# RF_AMPL_002.net
KiCad netlist of a schematic drawn in Altium Designer
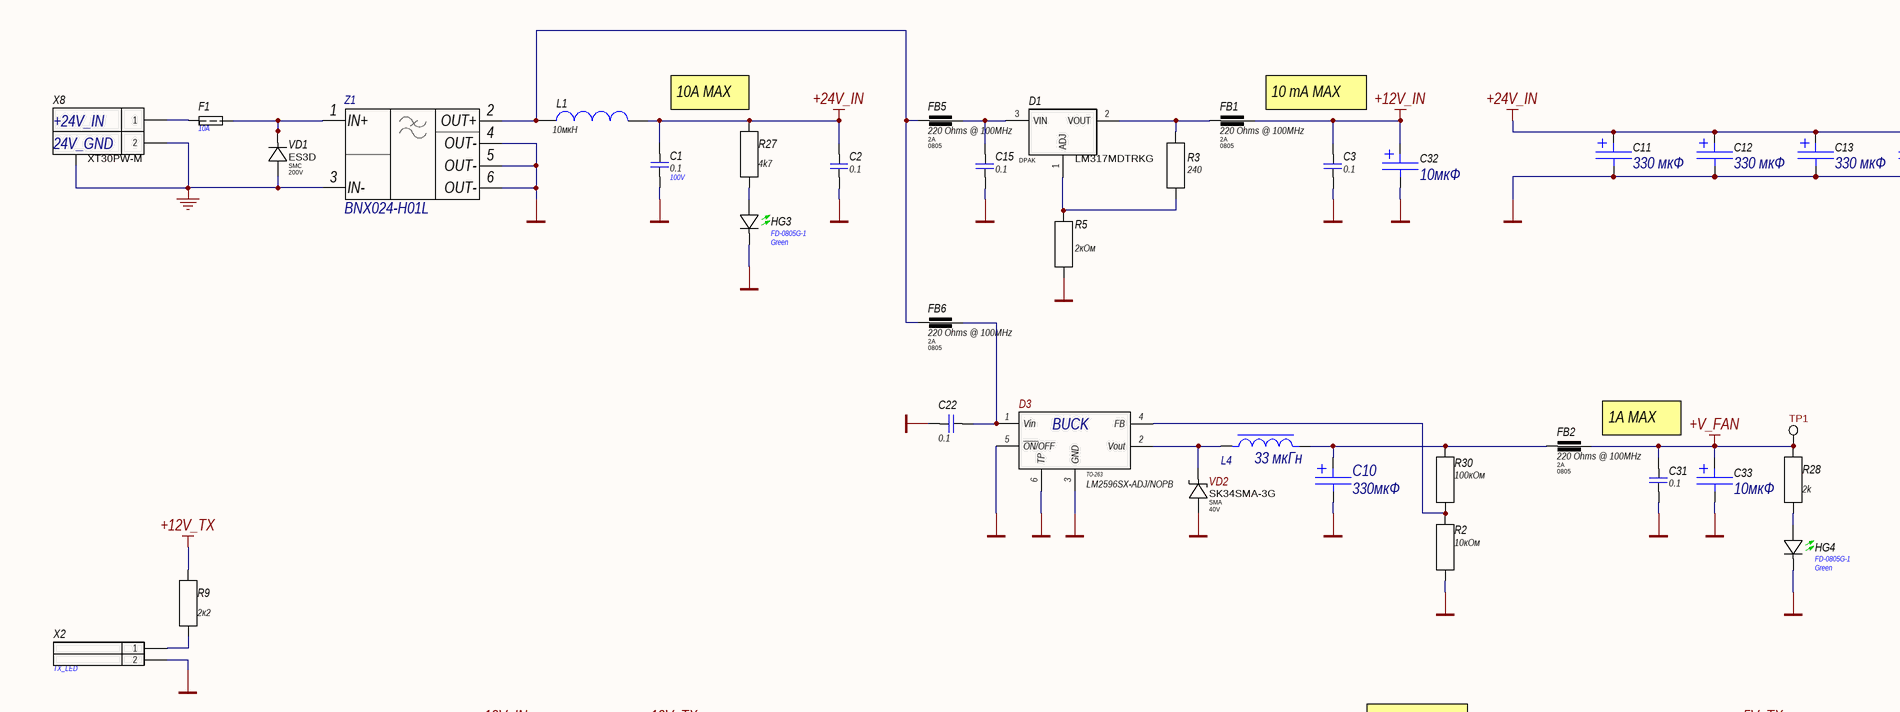
[diagram p0: RF_AMPL_002.SchDoc, top left]
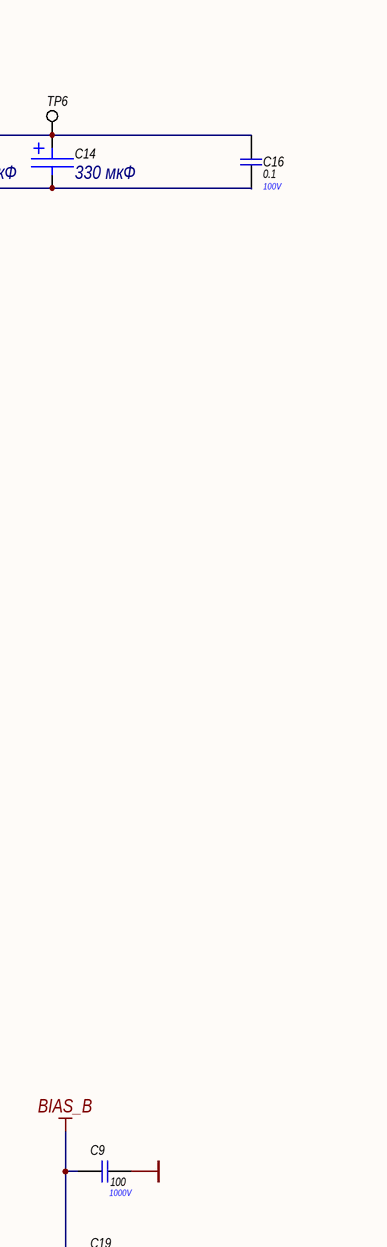
[diagram p1: RF_AMPL_002.SchDoc, top right]
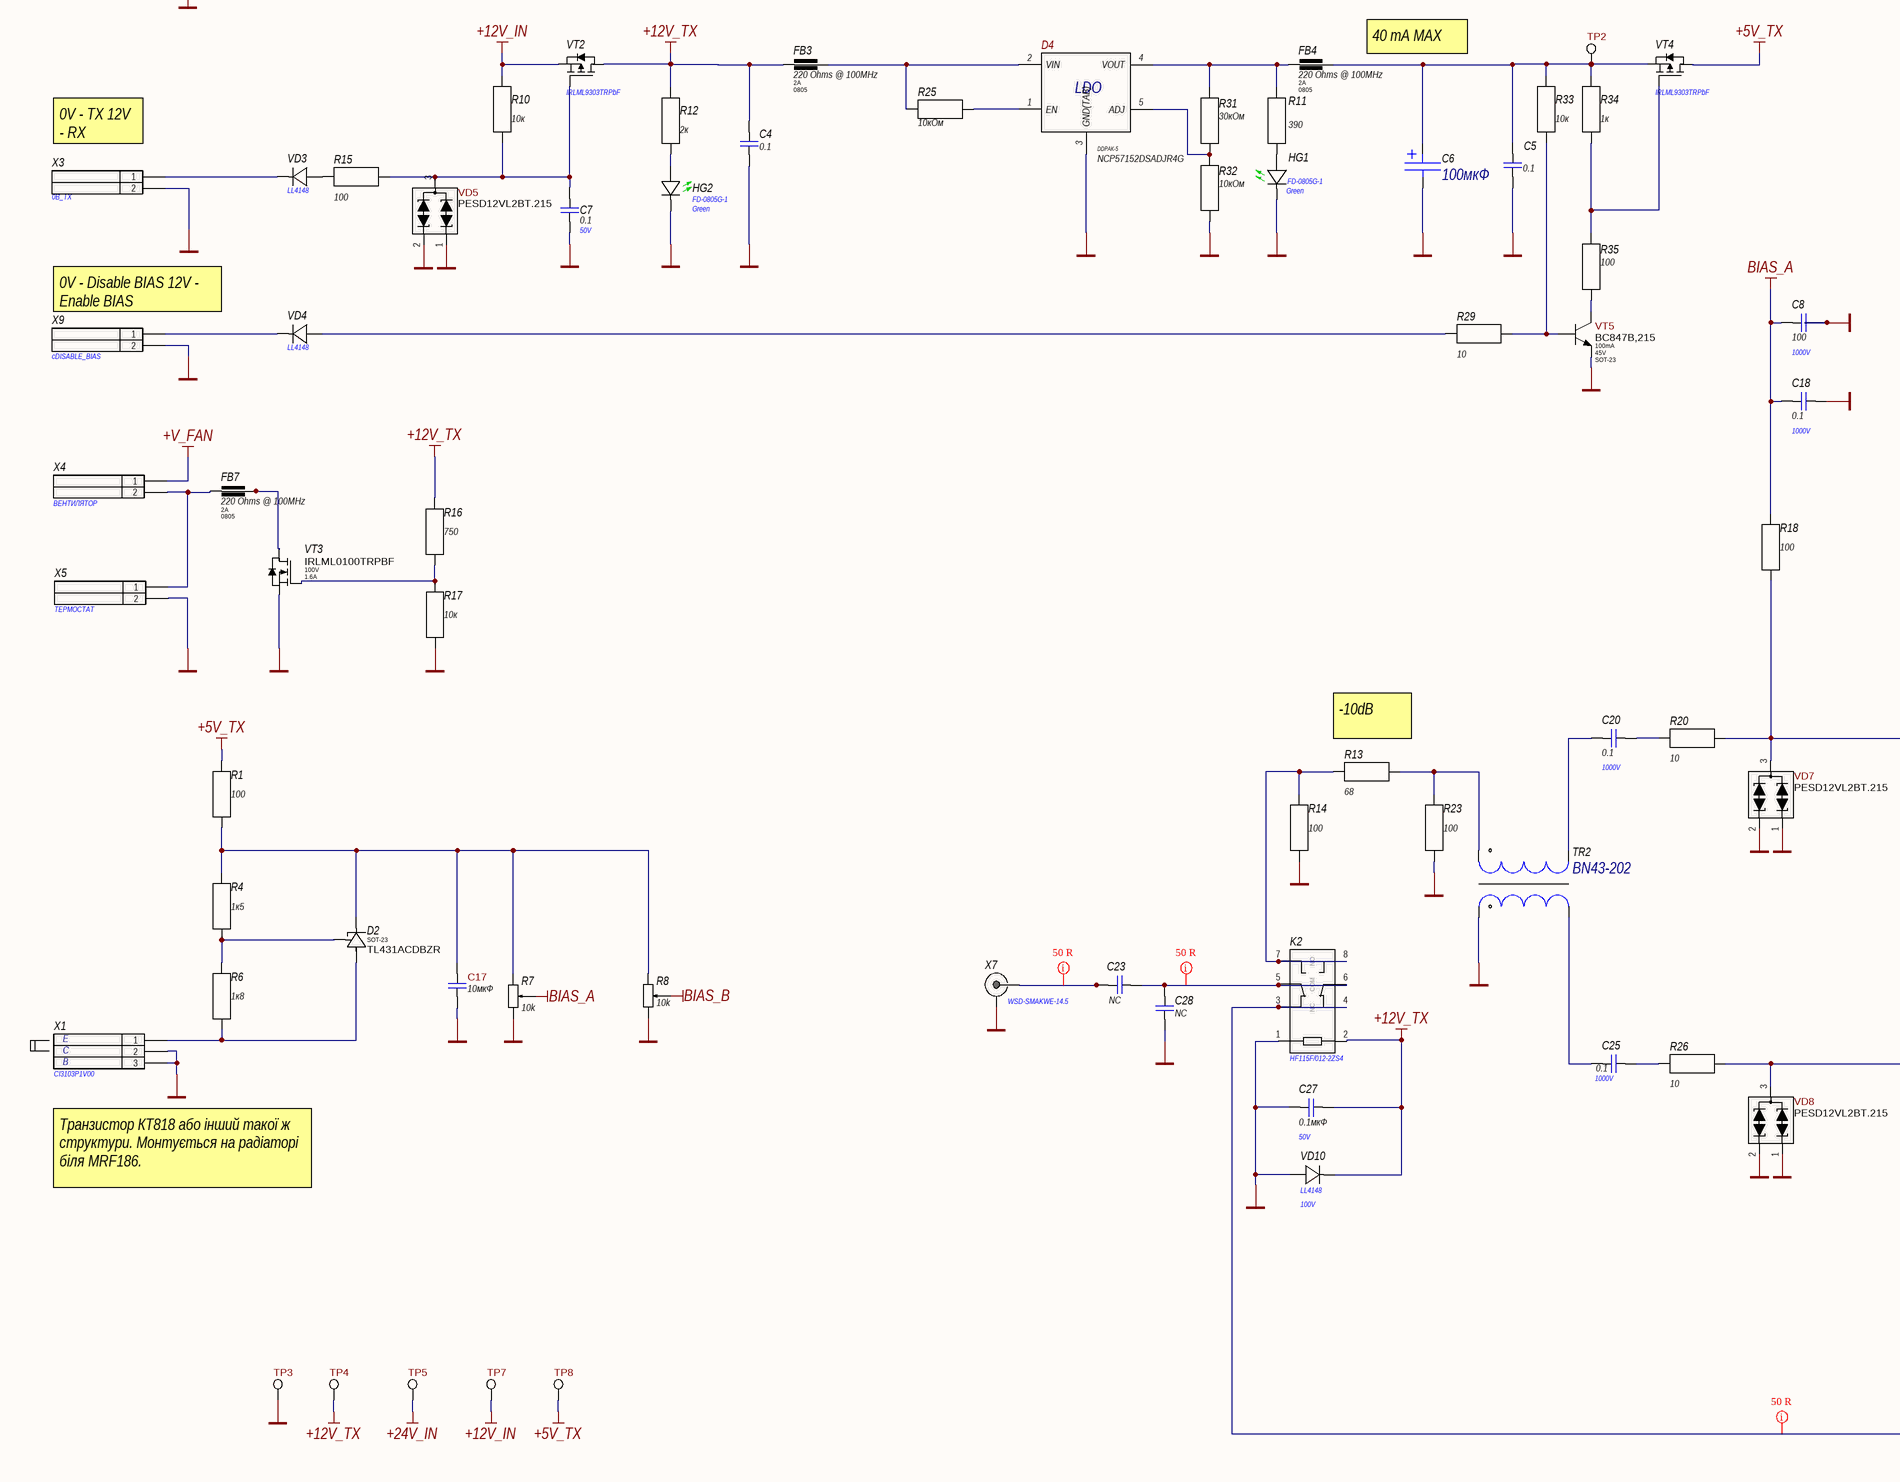
[diagram p2: RF_AMPL_002.SchDoc, bottom left]
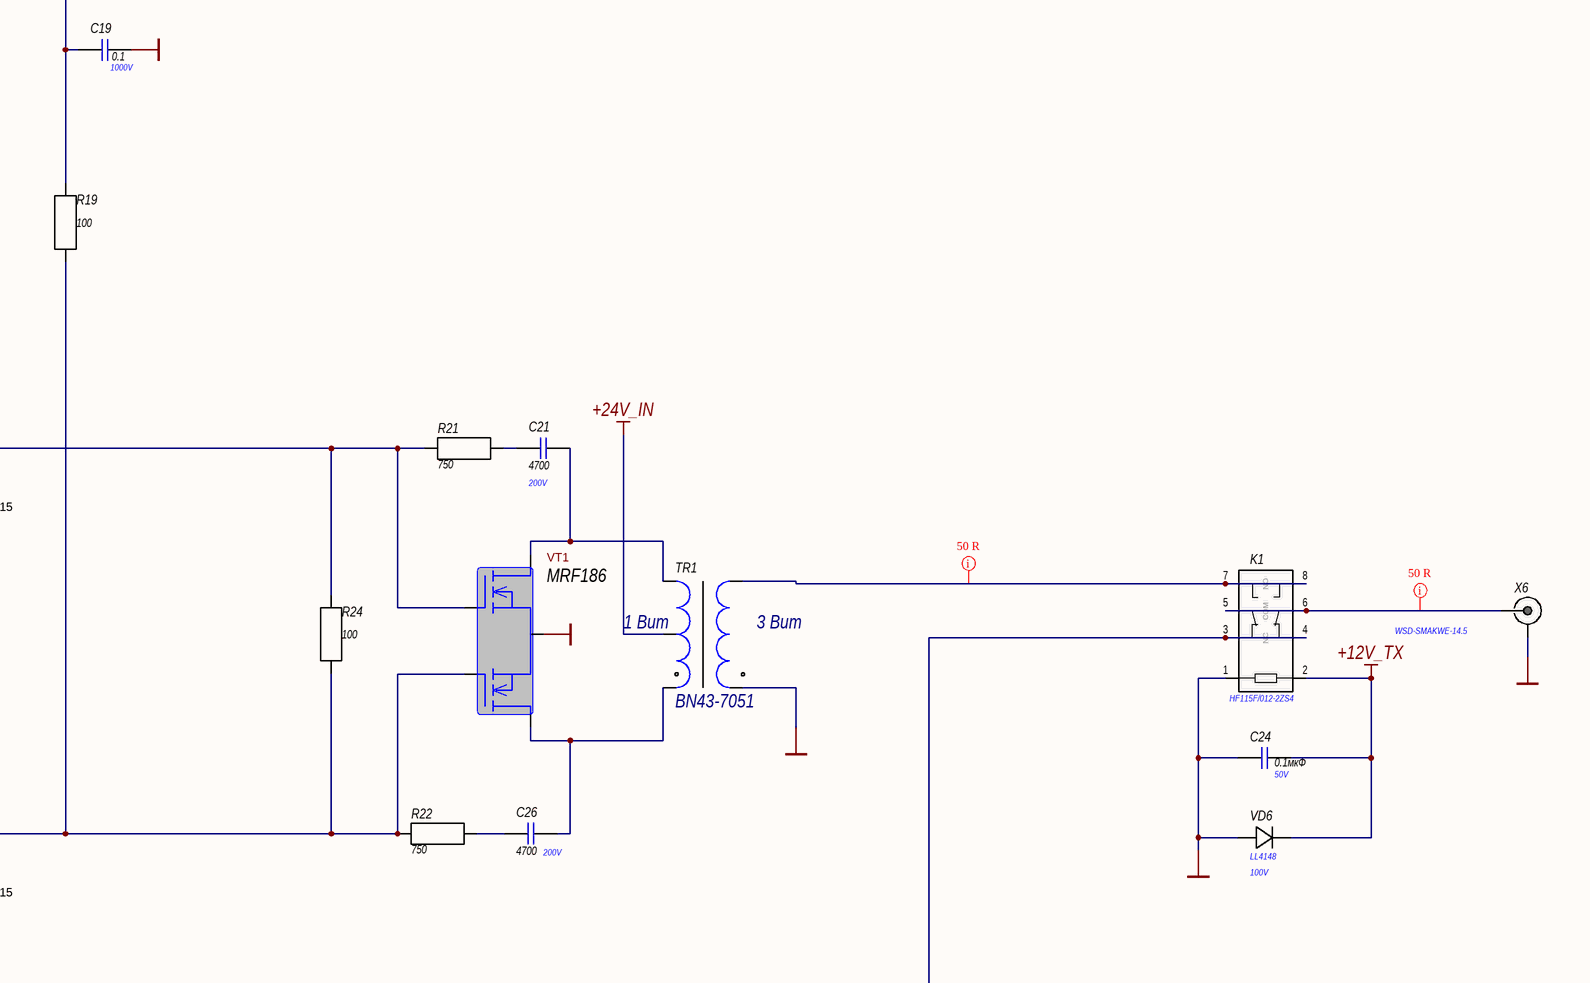
[diagram p3: RF_AMPL_002.SchDoc, bottom right]

(export (version "E")
  (design (tool "Eeschema 10.0.6"))
  (components
    (comp (ref "C1")
      (value "0.1")
      (footprint "C_CERAMIC_1206_MED")
      (description "1nF 1000V X7R ±10% 1206 Ceramic Capacitor RoHS")
      (fields
        (field (name "VOLTAGE") "100V")
        (field (name "PART NUMBER") "1206B102K102CG")
        (field (name "MANUFACTURER") "Walsin")
      )
      (libsource (lib "vitech_capacitors") (part "1206B102K102CG"))
    )
    (comp (ref "C2")
      (value "0.1")
      (footprint "C_CERAMIC_1206_MED")
      (description "1nF 1000V X7R ±10% 1206 Ceramic Capacitor RoHS")
      (fields (field (name "VOLTAGE") "100V") (field (name "PART NUMBER") "1206B102K102CG"))
      (libsource (lib "vitech_capacitors") (part "1206B102K102CG"))
    )
    (comp (ref "C3")
      (value "0.1")
      (footprint "C_CERAMIC_1206_MED")
      (description "1nF 1000V X7R ±10% 1206 Ceramic Capacitor RoHS")
      (fields (field (name "VOLTAGE") "100V") (field (name "PART NUMBER") "1206B102K102CG"))
      (libsource (lib "vitech_capacitors") (part "1206B102K102CG"))
    )
    (comp (ref "C4")
      (value "0.1")
      (footprint "C_CERAMIC_1206_MED")
      (description "1nF 1000V X7R ±10% 1206 Ceramic Capacitor RoHS")
      (fields (field (name "VOLTAGE") "100V") (field (name "PART NUMBER") "1206B102K102CG"))
      (libsource (lib "vitech_capacitors") (part "1206B102K102CG"))
    )
    (comp (ref "C5")
      (value "0.1")
      (footprint "C_CERAMIC_1206_MED")
      (description "1nF 1000V X7R ±10% 1206 Ceramic Capacitor RoHS")
      (fields (field (name "VOLTAGE") "100V") (field (name "PART NUMBER") "1206B102K102CG"))
      (libsource (lib "vitech_capacitors") (part "1206B102K102CG"))
    )
    (comp (ref "C6")
      (value "100мкФ")
      (footprint "CAPM_CASE_D_7.3x4.3x3.1mm")
      (description "Capacitor Tantalum *pF ±*% *V Case D")
      (fields (field (name "MANUFACTURER") "AVX") (field (name "PART NUMBER") "TAJD107M016R"))
      (libsource (lib "Passive") (part "CAP_TANTALUM_POLAR_CASE_D"))
    )
    (comp (ref "C7")
      (value "0.1")
      (footprint "C_CERAMIC_1206_MED")
      (description "1nF 1000V X7R ±10% 1206 Ceramic Capacitor RoHS")
      (fields
        (field (name "VOLTAGE") "50V")
        (field (name "PART NUMBER") "1206B102K102CG")
        (field (name "MANUFACTURER") "Walsin")
      )
      (libsource (lib "vitech_capacitors") (part "1206B102K102CG"))
    )
    (comp (ref "C8")
      (value "100")
      (footprint "C_CERAMIC_1206_MED")
      (description "1nF 1000V X7R ±10% 1206 Ceramic Capacitor RoHS")
      (fields
        (field (name "VOLTAGE") "1000V")
        (field (name "PART NUMBER") "1206B102K102CG")
        (field (name "MANUFACTURER") "Walsin")
      )
      (libsource (lib "vitech_capacitors") (part "1206B102K102CG"))
    )
    (comp (ref "C9")
      (value "100")
      (footprint "C_CERAMIC_1206_MED")
      (description "1nF 1000V X7R ±10% 1206 Ceramic Capacitor RoHS")
      (fields
        (field (name "VOLTAGE") "1000V")
        (field (name "PART NUMBER") "1206B102K102CG")
        (field (name "MANUFACTURER") "Walsin")
      )
      (libsource (lib "vitech_capacitors") (part "1206B102K102CG"))
    )
    (comp (ref "C10")
      (value "330мкФ")
      (footprint "CAPA_CASE_F_Panasonic_FT")
      (description "Capacitor Electrolytic *pF ±*% *V Case F")
      (fields (field (name "MANUFACTURER") "Panasonic") (field (name "PART NUMBER") "EEEFK1C331P"))
      (libsource (lib "Passive") (part "CAP_ELECTROLYTIC_POLAR_CASE_F_Panasonic_FT"))
    )
    (comp (ref "C11")
      (value "330 мкФ")
      (footprint "CAPA_CASE_G_10.4x10.4x10.5mm")
      (description "Capacitor Electrolytic *pF ±*% *V Case G")
      (fields (field (name "TOLERANCE") "±*%") (field (name "VOLTAGE") "*В"))
      (libsource (lib "Passive") (part "CAP_ELECTROLYTIC_POLAR_CASE_G"))
    )
    (comp (ref "C12")
      (value "330 мкФ")
      (footprint "CAPA_CASE_G_10.4x10.4x10.5mm")
      (description "Capacitor Electrolytic *pF ±*% *V Case G")
      (fields (field (name "TOLERANCE") "±*%") (field (name "VOLTAGE") "*В"))
      (libsource (lib "Passive") (part "CAP_ELECTROLYTIC_POLAR_CASE_G"))
    )
    (comp (ref "C13")
      (value "330 мкФ")
      (footprint "CAPA_CASE_G_10.4x10.4x10.5mm")
      (description "Capacitor Electrolytic *pF ±*% *V Case G")
      (fields (field (name "TOLERANCE") "±*%") (field (name "VOLTAGE") "*В"))
      (libsource (lib "Passive") (part "CAP_ELECTROLYTIC_POLAR_CASE_G"))
    )
    (comp (ref "C14")
      (value "330 мкФ")
      (footprint "CAPA_CASE_G_10.4x10.4x10.5mm")
      (description "Capacitor Electrolytic *pF ±*% *V Case G")
      (fields (field (name "TOLERANCE") "±*%") (field (name "VOLTAGE") "*В"))
      (libsource (lib "Passive") (part "CAP_ELECTROLYTIC_POLAR_CASE_G"))
    )
    (comp (ref "C15")
      (value "0.1")
      (footprint "C_CERAMIC_1206_MED")
      (description "1nF 1000V X7R ±10% 1206 Ceramic Capacitor RoHS")
      (fields (field (name "VOLTAGE") "100V") (field (name "PART NUMBER") "1206B102K102CG"))
      (libsource (lib "vitech_capacitors") (part "1206B102K102CG"))
    )
    (comp (ref "C16")
      (value "0.1")
      (footprint "C_CERAMIC_1206_MED")
      (description "1nF 1000V X7R ±10% 1206 Ceramic Capacitor RoHS")
      (fields
        (field (name "VOLTAGE") "100V")
        (field (name "PART NUMBER") "1206B102K102CG")
        (field (name "MANUFACTURER") "Walsin")
      )
      (libsource (lib "vitech_capacitors") (part "1206B102K102CG"))
    )
    (comp (ref "C17")
      (value "10мкФ")
      (footprint "C_CERAMIC_0805_HI")
      (fields
        (field (name "VOLTAGE") "50V")
        (field (name "PART NUMBER") "**")
        (field (name "MANUFACTURER") "Hitano")
      )
      (libsource (lib "vitech_capacitors") (part "CERAMIC_0805"))
    )
    (comp (ref "C18")
      (value "0.1")
      (footprint "C_CERAMIC_1206_MED")
      (description "1nF 1000V X7R ±10% 1206 Ceramic Capacitor RoHS")
      (fields
        (field (name "VOLTAGE") "1000V")
        (field (name "PART NUMBER") "1206B102K102CG")
        (field (name "MANUFACTURER") "Walsin")
      )
      (libsource (lib "vitech_capacitors") (part "1206B102K102CG"))
    )
    (comp (ref "C19")
      (value "0.1")
      (footprint "C_CERAMIC_1206_MED")
      (description "1nF 1000V X7R ±10% 1206 Ceramic Capacitor RoHS")
      (fields
        (field (name "VOLTAGE") "1000V")
        (field (name "PART NUMBER") "1206B102K102CG")
        (field (name "MANUFACTURER") "Walsin")
      )
      (libsource (lib "vitech_capacitors") (part "1206B102K102CG"))
    )
    (comp (ref "C20")
      (value "0.1")
      (footprint "C_CERAMIC_1206_MED")
      (description "1nF 1000V X7R ±10% 1206 Ceramic Capacitor RoHS")
      (fields
        (field (name "VOLTAGE") "1000V")
        (field (name "PART NUMBER") "1206B102K102CG")
        (field (name "MANUFACTURER") "Walsin")
      )
      (libsource (lib "vitech_capacitors") (part "1206B102K102CG"))
    )
    (comp (ref "C21")
      (value "4700")
      (footprint "C_CERAMIC_1206_MED")
      (description "1nF 1000V X7R ±10% 1206 Ceramic Capacitor RoHS")
      (fields
        (field (name "VOLTAGE") "200V")
        (field (name "PART NUMBER") "12065A472JAT2A")
        (field (name "MANUFACTURER") "Walsin")
      )
      (libsource (lib "vitech_capacitors") (part "1206B102K102CG"))
    )
    (comp (ref "C22")
      (value "0.1")
      (footprint "C_CERAMIC_1206_MED")
      (description "1nF 1000V X7R ±10% 1206 Ceramic Capacitor RoHS")
      (fields (field (name "VOLTAGE") "100V") (field (name "PART NUMBER") "1206B102K102CG"))
      (libsource (lib "vitech_capacitors") (part "1206B102K102CG"))
    )
    (comp (ref "C23")
      (value "NC")
      (footprint "C_CERAMIC_0805_HI")
      (fields
        (field (name "PART NUMBER") "**")
        (field (name "MANUFACTURER") "Hitano")
        (field (name "TOLERANCE") "±5%")
      )
      (libsource (lib "vitech_capacitors") (part "CERAMIC_0805"))
    )
    (comp (ref "C24")
      (value "0.1мкФ")
      (footprint "C_CERAMIC_0805_HI")
      (fields
        (field (name "PART NUMBER") "**")
        (field (name "MANUFACTURER") "Hitano")
        (field (name "TOLERANCE") "±5%")
        (field (name "VOLTAGE") "50V")
      )
      (libsource (lib "vitech_capacitors") (part "CERAMIC_0805"))
    )
    (comp (ref "C25")
      (value "0.1")
      (footprint "C_CERAMIC_1206_MED")
      (description "1nF 1000V X7R ±10% 1206 Ceramic Capacitor RoHS")
      (fields
        (field (name "VOLTAGE") "1000V")
        (field (name "PART NUMBER") "1206B102K102CG")
        (field (name "MANUFACTURER") "Walsin")
      )
      (libsource (lib "vitech_capacitors") (part "1206B102K102CG"))
    )
    (comp (ref "C26")
      (value "4700")
      (footprint "C_CERAMIC_1206_MED")
      (description "1nF 1000V X7R ±10% 1206 Ceramic Capacitor RoHS")
      (fields
        (field (name "VOLTAGE") "200V")
        (field (name "PART NUMBER") "12065A472JAT2A")
        (field (name "MANUFACTURER") "Walsin")
      )
      (libsource (lib "vitech_capacitors") (part "1206B102K102CG"))
    )
    (comp (ref "C27")
      (value "0.1мкФ")
      (footprint "C_CERAMIC_0805_HI")
      (fields
        (field (name "PART NUMBER") "**")
        (field (name "MANUFACTURER") "Hitano")
        (field (name "TOLERANCE") "±5%")
        (field (name "VOLTAGE") "50V")
      )
      (libsource (lib "vitech_capacitors") (part "CERAMIC_0805"))
    )
    (comp (ref "C28")
      (value "NC")
      (footprint "C_CERAMIC_0805_HI")
      (fields
        (field (name "PART NUMBER") "**")
        (field (name "MANUFACTURER") "Hitano")
        (field (name "TOLERANCE") "±5%")
      )
      (libsource (lib "vitech_capacitors") (part "CERAMIC_0805"))
    )
    (comp (ref "C31")
      (value "0.1")
      (footprint "C_CERAMIC_1206_MED")
      (description "1nF 1000V X7R ±10% 1206 Ceramic Capacitor RoHS")
      (fields (field (name "VOLTAGE") "100V") (field (name "PART NUMBER") "1206B102K102CG"))
      (libsource (lib "vitech_capacitors") (part "1206B102K102CG"))
    )
    (comp (ref "C32")
      (value "10мкФ")
      (footprint "CAPM_CASE_B_3.5x2.8x2.1mm")
      (description "Capacitor Tantalum *pF ±*% *V Case B")
      (fields (field (name "TOLERANCE") "±*%") (field (name "VOLTAGE") "20"))
      (libsource (lib "Passive") (part "CAP_TANTALUM_POLAR_CASE_B"))
    )
    (comp (ref "C33")
      (value "10мкФ")
      (footprint "CAPM_CASE_B_3.5x2.8x2.1mm")
      (description "Capacitor Tantalum *pF ±*% *V Case B")
      (fields (field (name "TOLERANCE") "±*%") (field (name "VOLTAGE") "20"))
      (libsource (lib "Passive") (part "CAP_TANTALUM_POLAR_CASE_B"))
    )
    (comp (ref "D1")
      (value "LM317MDTRKG")
      (footprint "DPAK")
      (description "4.25V to 40V Input Linear Voltage Regulator, 1 Output 500mA, Adjustable, TO-252-3 (DPAK)")
      (fields
        (field (name "MANUFACTURER") "Onsemi")
        (field (name "PACKAGE") "DPAK")
        (field (name "PART NUMBER") "LM317MDTRKG")
      )
      (libsource (lib "vitech_ic") (part "LM317MDTRKG"))
    )
    (comp (ref "D2")
      (value "TL431ACDBZR")
      (footprint "SOT-23_MED")
      (description "Adjustable Precision Shunt Regulator, Accuracy 1%,  SOT-23-3")
      (fields
        (field (name "PACKAGE") "SOT-23")
        (field (name "PART NUMBER") "TL431ACDBZR")
        (field (name "MANUFACTURER") "Texas Instruments")
      )
      (libsource (lib "vitech_ic") (part "TL431ACDBZR"))
    )
    (comp (ref "D3")
      (value "LM2596SX-ADJ/NOPB")
      (footprint "TO-263-5-1")
      (description "SIMPLE SWITCHER Power Converter 150-kHz 3-A Step-Down Voltage Regulator")
      (fields
        (field (name "MANUFACTURER") "Texas Instruments")
        (field (name "PACKAGE") "TO-263")
        (field (name "PART NUMBER") "LM2596SX-ADJ/NOPB")
      )
      (libsource (lib "vitech_ic") (part "LM2596SX-ADJ/NOPB"))
    )
    (comp (ref "D4")
      (value "NCP57152DSADJR4G")
      (footprint "DDPAK-5")
      (description "1.24V to 13V Input Low Dropout Regulator, Adjustable, 1.5A, D2PAK-5")
      (fields
        (field (name "PACKAGE") "DDPAK-5")
        (field (name "PART NUMBER") "NCP57152DSADJR4G")
        (field (name "MANUFACTURER") "Onsemi")
      )
      (libsource (lib "vitech_ic") (part "NCP57152DSADJR4G"))
    )
    (comp (ref "F1")
      (value "STANDART_FUSE_HOLDER")
      (footprint "17861640001")
      (description "Automotive Fuse holder THT-Mount")
      (fields (field (name "MANUFACTURER_PART_NUMBER") "17861640001") (field (name "CURRENT") "10A"))
      (libsource (lib "vitech_fuses") (part "STANDART_FUSE_HOLDER"))
    )
    (comp (ref "FB1")
      (value "220 Ohms @ 100MHz")
      (footprint "BLM21PGxxxxN1-Series")
      (description "220 Ohms @ 100MHz Power Line Ferrite Bead 0805, 2A 45mOhm")
      (fields
        (field (name "CURRENT") "2A")
        (field (name "PACKAGE") "0805")
        (field (name "PART NUMBER") "BLM21PG221SN1D")
        (field (name "TOLERANCE") "±25%")
      )
      (libsource (lib "vitech_inductors") (part "BLM21PG221SN1D"))
    )
    (comp (ref "FB2")
      (value "220 Ohms @ 100MHz")
      (footprint "BLM21PGxxxxN1-Series")
      (description "220 Ohms @ 100MHz Power Line Ferrite Bead 0805, 2A 45mOhm")
      (fields
        (field (name "CURRENT") "2A")
        (field (name "PACKAGE") "0805")
        (field (name "PART NUMBER") "BLM21PG221SN1D")
        (field (name "TOLERANCE") "±25%")
      )
      (libsource (lib "vitech_inductors") (part "BLM21PG221SN1D"))
    )
    (comp (ref "FB3")
      (value "220 Ohms @ 100MHz")
      (footprint "BLM21PGxxxxN1-Series")
      (description "220 Ohms @ 100MHz Power Line Ferrite Bead 0805, 2A 45mOhm")
      (fields
        (field (name "CURRENT") "2A")
        (field (name "PACKAGE") "0805")
        (field (name "PART NUMBER") "BLM21PG221SN1D")
        (field (name "TOLERANCE") "±25%")
      )
      (libsource (lib "vitech_inductors") (part "BLM21PG221SN1D"))
    )
    (comp (ref "FB4")
      (value "220 Ohms @ 100MHz")
      (footprint "BLM21PGxxxxN1-Series")
      (description "220 Ohms @ 100MHz Power Line Ferrite Bead 0805, 2A 45mOhm")
      (fields
        (field (name "CURRENT") "2A")
        (field (name "PACKAGE") "0805")
        (field (name "PART NUMBER") "BLM21PG221SN1D")
        (field (name "TOLERANCE") "±25%")
      )
      (libsource (lib "vitech_inductors") (part "BLM21PG221SN1D"))
    )
    (comp (ref "FB5")
      (value "220 Ohms @ 100MHz")
      (footprint "BLM21PGxxxxN1-Series")
      (description "220 Ohms @ 100MHz Power Line Ferrite Bead 0805, 2A 45mOhm")
      (fields
        (field (name "CURRENT") "2A")
        (field (name "PACKAGE") "0805")
        (field (name "PART NUMBER") "BLM21PG221SN1D")
        (field (name "TOLERANCE") "±25%")
      )
      (libsource (lib "vitech_inductors") (part "BLM21PG221SN1D"))
    )
    (comp (ref "FB6")
      (value "220 Ohms @ 100MHz")
      (footprint "BLM21PGxxxxN1-Series")
      (description "220 Ohms @ 100MHz Power Line Ferrite Bead 0805, 2A 45mOhm")
      (fields
        (field (name "CURRENT") "2A")
        (field (name "PACKAGE") "0805")
        (field (name "PART NUMBER") "BLM21PG221SN1D")
        (field (name "TOLERANCE") "±25%")
      )
      (libsource (lib "vitech_inductors") (part "BLM21PG221SN1D"))
    )
    (comp (ref "FB7")
      (value "220 Ohms @ 100MHz")
      (footprint "BLM21PGxxxxN1-Series")
      (description "220 Ohms @ 100MHz Power Line Ferrite Bead 0805, 2A 45mOhm")
      (fields
        (field (name "CURRENT") "2A")
        (field (name "PACKAGE") "0805")
        (field (name "PART NUMBER") "BLM21PG221SN1D")
        (field (name "TOLERANCE") "±25%")
      )
      (libsource (lib "vitech_inductors") (part "BLM21PG221SN1D"))
    )
    (comp (ref "HG1")
      (value "LTST-C171GKT")
      (footprint "LTST-C171GKT")
      (description "Low Power LED, Green 565nm, Clear, SMD 0805, Vf 2.1V - 2.6V, 5 ~ 12mcd @ 20 mA, 130°")
      (fields
        (field (name "PART NUMBER") "FD-0805G-1")
        (field (name "COLOR") "Green")
        (field (name "MANUFACTURER") "Lite-On Optoelectronics")
      )
      (libsource (lib "vitech_opto") (part "LTST-C171GKT"))
    )
    (comp (ref "HG2")
      (value "LTST-C171GKT")
      (footprint "LTST-C171GKT")
      (description "Low Power LED, Green 565nm, Clear, SMD 0805, Vf 2.1V - 2.6V, 5 ~ 12mcd @ 20 mA, 130°")
      (fields
        (field (name "PART NUMBER") "FD-0805G-1")
        (field (name "COLOR") "Green")
        (field (name "MANUFACTURER") "Lite-On Optoelectronics")
      )
      (libsource (lib "vitech_opto") (part "LTST-C171GKT"))
    )
    (comp (ref "HG3")
      (value "LTST-C171GKT")
      (footprint "LTST-C171GKT")
      (description "Low Power LED, Green 565nm, Clear, SMD 0805, Vf 2.1V - 2.6V, 5 ~ 12mcd @ 20 mA, 130°")
      (fields
        (field (name "PART NUMBER") "FD-0805G-1")
        (field (name "COLOR") "Green")
        (field (name "MANUFACTURER") "Lite-On Optoelectronics")
      )
      (libsource (lib "vitech_opto") (part "LTST-C171GKT"))
    )
    (comp (ref "HG4")
      (value "LTST-C171GKT")
      (footprint "LTST-C171GKT")
      (description "Low Power LED, Green 565nm, Clear, SMD 0805, Vf 2.1V - 2.6V, 5 ~ 12mcd @ 20 mA, 130°")
      (fields
        (field (name "PART NUMBER") "FD-0805G-1")
        (field (name "COLOR") "Green")
        (field (name "MANUFACTURER") "Lite-On Optoelectronics")
      )
      (libsource (lib "vitech_opto") (part "LTST-C171GKT"))
    )
    (comp (ref "K1")
      (value "HF115F/012-2ZS4")
      (footprint "HF115Fxxx-1(2)Zx3(4)")
      (description "Miniature High Power Relay, DPDT (2 Form C), 12VDC 400mW Coil, 5.0mm 2 Pole 8A AgCdO")
      (fields (field (name "PART NUMBER") "HF115F/012-2ZS4") (field (name "MANUFACTURER") "Hongfa"))
      (libsource (lib "vitech_electromechanics") (part "HF115F/012-2ZS4"))
    )
    (comp (ref "K2")
      (value "HF115F/012-2ZS4")
      (footprint "HF115Fxxx-1(2)Zx3(4)")
      (description "Miniature High Power Relay, DPDT (2 Form C), 12VDC 400mW Coil, 5.0mm 2 Pole 8A AgCdO")
      (fields (field (name "PART NUMBER") "HF115F/012-2ZS4") (field (name "MANUFACTURER") "Hongfa"))
      (libsource (lib "vitech_electromechanics") (part "HF115F/012-2ZS4"))
    )
    (comp (ref "L1")
      (value "10мкH")
      (footprint "IND: R22.9/14/7.62 (H)")
      (fields
        (field (name "MANUFACTURER") "Magnetics")
        (field (name "PARTNUMBER") "0077310A7")
        (field (name "VALUEMANUFACTURERPARTNUMBER") "Fixed inductor, 10мкH, ±20%, R22.9/14/7.62, Kool Mu, µ=125, 90 нГн/витков2")
      )
      (libsource (lib "inductor") (part "Inductor_R22.9/14/7.62"))
    )
    (comp (ref "L4")
      (value "33 мкГн")
      (footprint "INDPWR_Sumida_CDRH127/LD_INDM120120X80N")
      (description "FIXED IND  UH   A  MOHM SMD")
      (fields (field (name "MANUFACTURER") "Sumida") (field (name "PART NUMBER") "CDRH127/LD"))
      (libsource (lib "Passive") (part "INDPWR_Sumida_CDRH127/LD"))
    )
    (comp (ref "R1")
      (value "100")
      (footprint "R_ANY_CHIP_0805_HI")
      (description "RES 0.47 OHM 1% 1/8W 0805")
      (fields
        (field (name "MANUFACTURER") "Panasonic Electronic Components")
        (field (name "PART NUMBER") "ERJ-3RQFR47V")
      )
      (libsource (lib "vitech_resistors") (part "RES_0805"))
    )
    (comp (ref "R2")
      (value "10кОм")
      (footprint "R_ANY_CHIP_0805_HI")
      (description "RES 0.47 OHM 1% 1/8W 0805")
      (fields
        (field (name "MANUFACTURER") "Panasonic Electronic Components")
        (field (name "PART NUMBER") "ERJ-3RQFR47V")
      )
      (libsource (lib "vitech_resistors") (part "RES_0805"))
    )
    (comp (ref "R3")
      (value "240")
      (footprint "R_ANY_CHIP_0805_HI")
      (description "RES 0.47 OHM 1% 1/8W 0805")
      (fields
        (field (name "MANUFACTURER") "Panasonic Electronic Components")
        (field (name "PART NUMBER") "ERJ-3RQFR47V")
      )
      (libsource (lib "") (part "RES_0805_1"))
    )
    (comp (ref "R4")
      (value "1к5")
      (footprint "R_ANY_CHIP_0805_HI")
      (description "RES 0.47 OHM 1% 1/8W 0805")
      (fields
        (field (name "MANUFACTURER") "Panasonic Electronic Components")
        (field (name "PART NUMBER") "ERJ-3RQFR47V")
      )
      (libsource (lib "vitech_resistors") (part "RES_0805"))
    )
    (comp (ref "R5")
      (value "2кОм")
      (footprint "R_ANY_CHIP_0805_HI")
      (description "RES 0.47 OHM 1% 1/8W 0805")
      (fields
        (field (name "MANUFACTURER") "Panasonic Electronic Components")
        (field (name "PART NUMBER") "ERJ-3RQFR47V")
      )
      (libsource (lib "") (part "RES_0805_1"))
    )
    (comp (ref "R6")
      (value "1к8")
      (footprint "R_ANY_CHIP_0805_HI")
      (description "RES 0.47 OHM 1% 1/8W 0805")
      (fields
        (field (name "MANUFACTURER") "Panasonic Electronic Components")
        (field (name "PART NUMBER") "ERJ-3RQFR47V")
      )
      (libsource (lib "vitech_resistors") (part "RES_0805"))
    )
    (comp (ref "R7")
      (value "10k")
      (footprint "3296W-1-xxx")
      (description "10 kOhms ±10% Trimmer Resistor, 0.5W, Through Hole 3/8\", 4.83x9.53mm, 10.03mm Height")
      (fields (field (name "TOLERANCE") "±10%") (field (name "PART NUMBER") "3296W-1-103LF"))
      (libsource (lib "resistors") (part "3296W-1-103LF"))
    )
    (comp (ref "R8")
      (value "10k")
      (footprint "3296W-1-xxx")
      (description "10 kOhms ±10% Trimmer Resistor, 0.5W, Through Hole 3/8\", 4.83x9.53mm, 10.03mm Height")
      (fields (field (name "TOLERANCE") "±10%") (field (name "PART NUMBER") "3296W-1-103LF"))
      (libsource (lib "resistors") (part "3296W-1-103LF"))
    )
    (comp (ref "R9")
      (value "2к2")
      (footprint "R_ANY_CHIP_0805_HI")
      (description "RES 0.47 OHM 1% 1/8W 0805")
      (fields
        (field (name "MANUFACTURER") "Panasonic Electronic Components")
        (field (name "PART NUMBER") "ERJ-3RQFR47V")
      )
      (libsource (lib "") (part "RES_0805_1"))
    )
    (comp (ref "R10")
      (value "10к")
      (footprint "R_ANY_CHIP_0805_HI")
      (description "RES 0.47 OHM 1% 1/8W 0805")
      (fields
        (field (name "MANUFACTURER") "Panasonic Electronic Components")
        (field (name "PART NUMBER") "ERJ-3RQFR47V")
      )
      (libsource (lib "") (part "RES_0805_1"))
    )
    (comp (ref "R11")
      (value "390")
      (footprint "R_ANY_CHIP_0805_HI")
      (description "RES 0.47 OHM 1% 1/8W 0805")
      (fields
        (field (name "MANUFACTURER") "Panasonic Electronic Components")
        (field (name "PART NUMBER") "ERJ-3RQFR47V")
      )
      (libsource (lib "") (part "RES_0805_1"))
    )
    (comp (ref "R12")
      (value "2к")
      (footprint "R_ANY_CHIP_0805_HI")
      (description "RES 0.47 OHM 1% 1/8W 0805")
      (fields
        (field (name "MANUFACTURER") "Panasonic Electronic Components")
        (field (name "PART NUMBER") "ERJ-3RQFR47V")
      )
      (libsource (lib "vitech_resistors") (part "RES_0805"))
    )
    (comp (ref "R13")
      (value "68")
      (footprint "FKN2WS-Series")
      (description "RESISTORS THT")
      (fields
        (field (name "MANUFACTURER") "Panasonic Electronic Components")
        (field (name "PART NUMBER") "ERJ-3RQFR47V")
      )
      (libsource (lib "") (part "RES_THT_2"))
    )
    (comp (ref "R14")
      (value "100")
      (footprint "FKN2WS-Series")
      (description "RESISTORS THT")
      (fields
        (field (name "MANUFACTURER") "Panasonic Electronic Components")
        (field (name "PART NUMBER") "ERJ-3RQFR47V")
      )
      (libsource (lib "vitech_resistors") (part "RES_THT"))
    )
    (comp (ref "R15")
      (value "100")
      (footprint "R_ANY_CHIP_0805_HI")
      (description "RES 0.47 OHM 1% 1/8W 0805")
      (fields
        (field (name "MANUFACTURER") "Panasonic Electronic Components")
        (field (name "PART NUMBER") "ERJ-3RQFR47V")
      )
      (libsource (lib "") (part "RES_0805_3"))
    )
    (comp (ref "R16")
      (value "750")
      (footprint "R_ANY_CHIP_0805_HI")
      (description "RES 0.47 OHM 1% 1/8W 0805")
      (fields
        (field (name "MANUFACTURER") "Panasonic Electronic Components")
        (field (name "PART NUMBER") "ERJ-3RQFR47V")
      )
      (libsource (lib "vitech_resistors") (part "RES_0805"))
    )
    (comp (ref "R17")
      (value "10к")
      (footprint "R_ANY_CHIP_0805_HI")
      (description "RES 0.47 OHM 1% 1/8W 0805")
      (fields
        (field (name "MANUFACTURER") "Panasonic Electronic Components")
        (field (name "PART NUMBER") "ERJ-3RQFR47V")
      )
      (libsource (lib "") (part "RES_0805_1"))
    )
    (comp (ref "R18")
      (value "100")
      (footprint "R_ANY_CHIP_0805_HI")
      (description "RES 0.47 OHM 1% 1/8W 0805")
      (fields
        (field (name "MANUFACTURER") "Panasonic Electronic Components")
        (field (name "PART NUMBER") "ERJ-3RQFR47V")
      )
      (libsource (lib "vitech_resistors") (part "RES_0805"))
    )
    (comp (ref "R19")
      (value "100")
      (footprint "R_ANY_CHIP_0805_HI")
      (description "RES 0.47 OHM 1% 1/8W 0805")
      (fields
        (field (name "MANUFACTURER") "Panasonic Electronic Components")
        (field (name "PART NUMBER") "ERJ-3RQFR47V")
      )
      (libsource (lib "vitech_resistors") (part "RES_0805"))
    )
    (comp (ref "R20")
      (value "10")
      (footprint "R_ANY_CHIP_0805_HI")
      (description "RES 0.47 OHM 1% 1/8W 0805")
      (fields
        (field (name "MANUFACTURER") "Panasonic Electronic Components")
        (field (name "PART NUMBER") "ERJ-3RQFR47V")
      )
      (libsource (lib "") (part "RES_0805_2"))
    )
    (comp (ref "R21")
      (value "750")
      (footprint "FKN2WS-Series")
      (description "RESISTORS THT")
      (fields
        (field (name "MANUFACTURER") "Panasonic Electronic Components")
        (field (name "PART NUMBER") "ERJ-3RQFR47V")
      )
      (libsource (lib "") (part "RES_THT_1"))
    )
    (comp (ref "R22")
      (value "750")
      (footprint "FKN2WS-Series")
      (description "RESISTORS THT")
      (fields
        (field (name "MANUFACTURER") "Panasonic Electronic Components")
        (field (name "PART NUMBER") "ERJ-3RQFR47V")
      )
      (libsource (lib "") (part "RES_THT_1"))
    )
    (comp (ref "R23")
      (value "100")
      (footprint "FKN2WS-Series")
      (description "RESISTORS THT")
      (fields
        (field (name "MANUFACTURER") "Panasonic Electronic Components")
        (field (name "PART NUMBER") "ERJ-3RQFR47V")
      )
      (libsource (lib "vitech_resistors") (part "RES_THT"))
    )
    (comp (ref "R24")
      (value "100")
      (footprint "FKN2WS-Series")
      (description "RESISTORS THT")
      (fields
        (field (name "MANUFACTURER") "Panasonic Electronic Components")
        (field (name "PART NUMBER") "ERJ-3RQFR47V")
      )
      (libsource (lib "vitech_resistors") (part "RES_THT"))
    )
    (comp (ref "R25")
      (value "10кОм")
      (footprint "R_ANY_CHIP_0805_HI")
      (description "RES 0.47 OHM 1% 1/8W 0805")
      (fields
        (field (name "MANUFACTURER") "Panasonic Electronic Components")
        (field (name "PART NUMBER") "ERJ-3RQFR47V")
      )
      (libsource (lib "") (part "RES_0805_2"))
    )
    (comp (ref "R26")
      (value "10")
      (footprint "R_ANY_CHIP_0805_HI")
      (description "RES 0.47 OHM 1% 1/8W 0805")
      (fields
        (field (name "MANUFACTURER") "Panasonic Electronic Components")
        (field (name "PART NUMBER") "ERJ-3RQFR47V")
      )
      (libsource (lib "") (part "RES_0805_2"))
    )
    (comp (ref "R27")
      (value "4k7")
      (footprint "R_ANY_CHIP_0805_HI")
      (description "RES 0.47 OHM 1% 1/8W 0805")
      (fields
        (field (name "MANUFACTURER") "Panasonic Electronic Components")
        (field (name "PART NUMBER") "ERJ-3RQFR47V")
      )
      (libsource (lib "vitech_resistors") (part "RES_0805"))
    )
    (comp (ref "R28")
      (value "2k")
      (footprint "R_ANY_CHIP_0805_HI")
      (description "RES 0.47 OHM 1% 1/8W 0805")
      (fields
        (field (name "MANUFACTURER") "Panasonic Electronic Components")
        (field (name "PART NUMBER") "ERJ-3RQFR47V")
      )
      (libsource (lib "vitech_resistors") (part "RES_0805"))
    )
    (comp (ref "R29")
      (value "10")
      (footprint "R_ANY_CHIP_0805_HI")
      (description "RES 0.47 OHM 1% 1/8W 0805")
      (fields
        (field (name "MANUFACTURER") "Panasonic Electronic Components")
        (field (name "PART NUMBER") "ERJ-3RQFR47V")
      )
      (libsource (lib "") (part "RES_0805_3"))
    )
    (comp (ref "R30")
      (value "100кОм")
      (footprint "R_ANY_CHIP_0805_HI")
      (description "100кОм 1% 1/8W 0805")
      (fields
        (field (name "MANUFACTURER") "Panasonic Electronic Components")
        (field (name "PART NUMBER") "ERJ-3RQFR47V")
      )
      (libsource (lib "vitech_resistors") (part "RES_0805"))
    )
    (comp (ref "R31")
      (value "30кОм")
      (footprint "R_ANY_CHIP_0805_HI")
      (description "RES 0.47 OHM 1% 1/8W 0805")
      (fields
        (field (name "MANUFACTURER") "Panasonic Electronic Components")
        (field (name "PART NUMBER") "ERJ-3RQFR47V")
      )
      (libsource (lib "vitech_resistors") (part "RES_0805"))
    )
    (comp (ref "R32")
      (value "10кОм")
      (footprint "R_ANY_CHIP_0805_HI")
      (description "RES 0.47 OHM 1% 1/8W 0805")
      (fields
        (field (name "MANUFACTURER") "Panasonic Electronic Components")
        (field (name "PART NUMBER") "ERJ-3RQFR47V")
      )
      (libsource (lib "vitech_resistors") (part "RES_0805"))
    )
    (comp (ref "R33")
      (value "10к")
      (footprint "R_ANY_CHIP_0805_HI")
      (description "RES 0.47 OHM 1% 1/8W 0805")
      (fields
        (field (name "MANUFACTURER") "Panasonic Electronic Components")
        (field (name "PART NUMBER") "ERJ-3RQFR47V")
      )
      (libsource (lib "") (part "RES_0805_1"))
    )
    (comp (ref "R34")
      (value "1к")
      (footprint "R_ANY_CHIP_0805_HI")
      (description "RES 0.47 OHM 1% 1/8W 0805")
      (fields
        (field (name "MANUFACTURER") "Panasonic Electronic Components")
        (field (name "PART NUMBER") "ERJ-3RQFR47V")
      )
      (libsource (lib "") (part "RES_0805_1"))
    )
    (comp (ref "R35")
      (value "100")
      (footprint "R_ANY_CHIP_0805_HI")
      (description "RES 0.47 OHM 1% 1/8W 0805")
      (fields
        (field (name "MANUFACTURER") "Panasonic Electronic Components")
        (field (name "PART NUMBER") "ERJ-3RQFR47V")
      )
      (libsource (lib "vitech_resistors") (part "RES_0805"))
    )
    (comp (ref "TP1")
      (value "PAD-0.96mm")
      (footprint "PAD-0.96mm")
      (description "0.96mm Pad for Plug-In or Receptacle")
      (fields (field (name "MANUFACTURER") "NONE"))
      (libsource (lib "probetools") (part "PAD-0.96mm"))
    )
    (comp (ref "TP2")
      (value "PAD-0.96mm")
      (footprint "PAD-0.96mm")
      (description "0.96mm Pad for Plug-In or Receptacle")
      (fields (field (name "MANUFACTURER") "NONE"))
      (libsource (lib "probetools") (part "PAD-0.96mm"))
    )
    (comp (ref "TP3")
      (value "PAD-0.96mm")
      (footprint "PAD-0.96mm")
      (description "0.96mm Pad for Plug-In or Receptacle")
      (fields (field (name "MANUFACTURER") "NONE"))
      (libsource (lib "probetools") (part "PAD-0.96mm"))
    )
    (comp (ref "TP4")
      (value "PAD-0.96mm")
      (footprint "PAD-0.96mm")
      (description "0.96mm Pad for Plug-In or Receptacle")
      (fields (field (name "MANUFACTURER") "NONE"))
      (libsource (lib "probetools") (part "PAD-0.96mm"))
    )
    (comp (ref "TP5")
      (value "PAD-0.96mm")
      (footprint "PAD-0.96mm")
      (description "0.96mm Pad for Plug-In or Receptacle")
      (fields (field (name "MANUFACTURER") "NONE"))
      (libsource (lib "probetools") (part "PAD-0.96mm"))
    )
    (comp (ref "TP6")
      (value "PAD-1.75mm")
      (footprint "PAD-1.75mm")
      (description "1.75mm Pad for Plug-In or Receptacle")
      (fields (field (name "MANUFACTURER") "NONE"))
      (libsource (lib "probetools") (part "PAD-1.75mm"))
    )
    (comp (ref "TP7")
      (value "PAD-0.96mm")
      (footprint "PAD-0.96mm")
      (description "0.96mm Pad for Plug-In or Receptacle")
      (fields (field (name "MANUFACTURER") "NONE"))
      (libsource (lib "probetools") (part "PAD-0.96mm"))
    )
    (comp (ref "TP8")
      (value "PAD-0.96mm")
      (footprint "PAD-0.96mm")
      (description "0.96mm Pad for Plug-In or Receptacle")
      (fields (field (name "MANUFACTURER") "NONE"))
      (libsource (lib "probetools") (part "PAD-0.96mm"))
    )
    (comp (ref "TR1")
      (value "TR")
      (footprint "Amidon_43-7051")
      (fields
        (field (name "MANUFACTURER") "Handmade")
        (field (name "TOLERANCE") "±20%")
        (field (name "PART NUMBER") "BN43-7051")
      )
      (libsource (lib "vitech_inductors") (part "Amidon_BN43-7051"))
    )
    (comp (ref "TR2")
      (value "TR")
      (footprint "Amidon_43-202")
      (fields
        (field (name "MANUFACTURER") "Handmade")
        (field (name "TOLERANCE") "±20%")
        (field (name "PART NUMBER") "BN43-202")
      )
      (libsource (lib "vitech_inductors") (part "Amidon_BN43-202"))
    )
    (comp (ref "VD1")
      (value "ES3D")
      (footprint "SMC")
      (description "Diode Standard 200V 3A, SMC")
      (fields
        (field (name "PART NUMBER") "ES3D")
        (field (name "PACKAGE") "SMC")
        (field (name "VOLTAGE") "200V")
        (field (name "MANUFACTURER") "Onsemi")
      )
      (libsource (lib "vitech_semiconductors") (part "ES3D"))
    )
    (comp (ref "VD2")
      (value "SK34SMA-3G")
      (footprint "SMA_MED")
      (description "Diode Schottky 40V 3A, SMA, Leakage Current 50uA")
      (fields
        (field (name "PART NUMBER") "SK34SMA-3G")
        (field (name "PACKAGE") "SMA")
        (field (name "VOLTAGE") "40V")
        (field (name "MANUFACTURER") "Diodec Semiconductor")
      )
      (libsource (lib "vitech_semiconductors") (part "SK34SMA-3G"))
    )
    (comp (ref "VD3")
      (value "LL4148")
      (footprint "SOD-80C_MED")
      (description "Fast Switching Diode, 100V 200 mA, SOD-80C")
      (fields
        (field (name "PART NUMBER") "LL4148")
        (field (name "VOLTAGE") "100V")
        (field (name "MANUFACTURER") "Suntan")
      )
      (libsource (lib "vitech_semiconductors") (part "LL4148"))
    )
    (comp (ref "VD4")
      (value "LL4148")
      (footprint "SOD-80C_MED")
      (description "Fast Switching Diode, 100V 200 mA, SOD-80C")
      (fields
        (field (name "PART NUMBER") "LL4148")
        (field (name "VOLTAGE") "100V")
        (field (name "MANUFACTURER") "Suntan")
      )
      (libsource (lib "vitech_semiconductors") (part "LL4148"))
    )
    (comp (ref "VD5")
      (value "PESD12VL2BT.215")
      (footprint "SOT-23_MED")
      (description "Double Bidirectional TVS Diode 26V Clamp, 15A (8/20us) Ipp, SOT-23")
      (fields
        (field (name "PART NUMBER") "PESD12VL2BT.215")
        (field (name "MANUFACTURER") "Nexperia USA")
        (field (name "VOLTAGE") "12V")
      )
      (libsource (lib "vitech_semiconductors") (part "PESD3V3L2BT,215"))
    )
    (comp (ref "VD6")
      (value "LL4148")
      (footprint "SOD-80C_MED")
      (description "Fast Switching Diode, 100V 200 mA, SOD-80C")
      (fields
        (field (name "PART NUMBER") "LL4148")
        (field (name "VOLTAGE") "100V")
        (field (name "MANUFACTURER") "Suntan")
      )
      (libsource (lib "vitech_semiconductors") (part "LL4148"))
    )
    (comp (ref "VD7")
      (value "PESD12VL2BT.215")
      (footprint "SOT-23_MED")
      (description "Double Bidirectional TVS Diode 26V Clamp, 15A (8/20us) Ipp, SOT-23")
      (fields
        (field (name "PART NUMBER") "PESD12VL2BT.215")
        (field (name "MANUFACTURER") "Nexperia USA")
        (field (name "VOLTAGE") "12V")
      )
      (libsource (lib "vitech_semiconductors") (part "PESD3V3L2BT,215"))
    )
    (comp (ref "VD8")
      (value "PESD12VL2BT.215")
      (footprint "SOT-23_MED")
      (description "Double Bidirectional TVS Diode 26V Clamp, 15A (8/20us) Ipp, SOT-23")
      (fields
        (field (name "PART NUMBER") "PESD12VL2BT.215")
        (field (name "MANUFACTURER") "Nexperia USA")
        (field (name "VOLTAGE") "12V")
      )
      (libsource (lib "vitech_semiconductors") (part "PESD3V3L2BT,215"))
    )
    (comp (ref "VD10")
      (value "LL4148")
      (footprint "SOD-80C_MED")
      (description "Fast Switching Diode, 100V 200 mA, SOD-80C")
      (fields
        (field (name "PART NUMBER") "LL4148")
        (field (name "VOLTAGE") "100V")
        (field (name "MANUFACTURER") "Suntan")
      )
      (libsource (lib "vitech_semiconductors") (part "LL4148"))
    )
    (comp (ref "VT1")
      (value "MRF186")
      (footprint "MRF186")
      (description "40V, 60A max N-Channel AlphaSGT Power MOSFET, 6.1mOhm @ Vgs = 10V")
      (fields (field (name "MANUFACTURER") "MOTOROLLA") (field (name "PART NUMBER") "MRF186"))
      (libsource (lib "vitech_semiconductors") (part "MRF186"))
    )
    (comp (ref "VT2")
      (value "IRLML9303TRPbF")
      (footprint "SOT-23_MED")
      (description "-30V, -3.6A max P-Channel HEXFET MOSFET, 82mOhm @ Vgs = -4.5V")
      (fields
        (field (name "MANUFACTURER") "Infineon Technologies")
        (field (name "PART NUMBER") "IRLML9301TRPbF")
      )
      (libsource (lib "vitech_semiconductors") (part "IRLML9301TRPbF"))
    )
    (comp (ref "VT3")
      (value "IRLML0100TR")
      (footprint "SOT-23_MED")
      (description "100V, 1.6A max N-Channel HEXFET Power MOSFET, 190mOhm @ Vgs = 4.5V")
      (fields
        (field (name "PART NUMBER") "IRLML0100TRPBF")
        (field (name "VDS") "100V")
        (field (name "ID") "1.6A")
        (field (name "MANUFACTURER") "Infineon Technologies")
      )
      (libsource (lib "vitech_semiconductors") (part "IRLML0100TRPBF"))
    )
    (comp (ref "VT4")
      (value "IRLML9303TRPbF")
      (footprint "SOT-23_MED")
      (description "-30V, -3.6A max P-Channel HEXFET MOSFET, 82mOhm @ Vgs = -4.5V")
      (fields
        (field (name "MANUFACTURER") "Infineon Technologies")
        (field (name "PART NUMBER") "IRLML9301TRPbF")
      )
      (libsource (lib "vitech_semiconductors") (part "IRLML9301TRPbF"))
    )
    (comp (ref "VT5")
      (value "BC847B")
      (footprint "SOT-23_MED")
      (description "45V, 100mA NPN General Purpose Transistor")
      (fields
        (field (name "PART NUMBER") "BC847B,215")
        (field (name "IC") "100mA")
        (field (name "VCE") "45V")
        (field (name "PACKAGE") "SOT-23")
        (field (name "MANUFACTURER") "Nexperia USA")
      )
      (libsource (lib "vitech_semiconductors") (part "BC847B,215"))
    )
    (comp (ref "X1")
      (value "WH-03S")
      (footprint "WF-3S")
      (description "WH Series 2.54mm Wire to Board Straight DIP Type Headers, 3 Pin")
      (fields (field (name "PART NUMBER") "CI3103P1V00") (field (name "MANUFACTURER") "CviLux"))
      (libsource (lib "vitech_connectors") (part "CI3103P1V00"))
    )
    (comp (ref "X2")
      (value "WH-02R")
      (footprint "WF-2R")
      (description "WH Series 2.54mm Wire to Board Right Angle DIP Type Headers, 2 Pin")
      (fields (field (name "PART NUMBER") "TX_LED") (field (name "MANUFACTURER") "CviLux"))
      (libsource (lib "vitech_connectors") (part "CI3102P1H00"))
    )
    (comp (ref "X3")
      (value "WH-02R")
      (footprint "WF-2R")
      (description "WH Series 2.54mm Wire to Board Right Angle DIP Type Headers, 2 Pin")
      (fields (field (name "PART NUMBER") "0B_TX") (field (name "MANUFACTURER") "CviLux"))
      (libsource (lib "vitech_connectors") (part "CI3102P1H00"))
    )
    (comp (ref "X4")
      (value "WH-02R")
      (footprint "WF-2R")
      (description "WH Series 2.54mm Wire to Board Right Angle DIP Type Headers, 2 Pin")
      (fields (field (name "PART NUMBER") "ВЕНТИЛЯТОР") (field (name "MANUFACTURER") "CviLux"))
      (libsource (lib "vitech_connectors") (part "CI3102P1H00"))
    )
    (comp (ref "X5")
      (value "WH-02R")
      (footprint "WF-2R")
      (description "WH Series 2.54mm Wire to Board Right Angle DIP Type Headers, 2 Pin")
      (fields (field (name "PART NUMBER") "ТЕРМОСТАТ") (field (name "MANUFACTURER") "CviLux"))
      (libsource (lib "vitech_connectors") (part "CI3102P1H00"))
    )
    (comp (ref "X6")
      (value "WSD-SMAKWE-14.5")
      (footprint "KLS1-SMA002")
      (description "50Ohm SMA Connector, Right Angle, Female, 5.1mm")
      (fields
        (field (name "PART NUMBER") "WSD-SMAKWE-14.5")
        (field (name "MANUFACTURER") "Wangshen Development LLC")
      )
      (libsource (lib "vitech_connectors") (part "WSD-SMAKWE-14.5"))
    )
    (comp (ref "X7")
      (value "WSD-SMAKWE-14.5")
      (footprint "KLS1-SMA002")
      (description "50Ohm SMA Connector, Right Angle, Female, 5.1mm")
      (fields
        (field (name "PART NUMBER") "WSD-SMAKWE-14.5")
        (field (name "MANUFACTURER") "Wangshen Development LLC")
      )
      (libsource (lib "") (part "WSD-SMAKWE-14.5_1"))
    )
    (comp (ref "X8")
      (value "XT30PW-M")
      (footprint "XT30PW-M")
      (description "2 Pin DC Power Socket, XT30, Male, THT, Right Angle, Yellow, 15A, 500V")
      (fields (field (name "PART NUMBER") "XT30PW-M") (field (name "MANUFACTURER") "Amass"))
      (libsource (lib "vitech_connectors") (part "XT30PW-M"))
    )
    (comp (ref "X9")
      (value "WH-02R")
      (footprint "WF-2R")
      (description "WH Series 2.54mm Wire to Board Right Angle DIP Type Headers, 2 Pin")
      (fields (field (name "PART NUMBER") "cDISABLE_BIAS") (field (name "MANUFACTURER") "CviLux"))
      (libsource (lib "vitech_connectors") (part "CI3102P1H00"))
    )
    (comp (ref "Z1")
      (value "~")
      (footprint "Murata_BNX02xH01x")
      (description "LC EMI Filter 5th Order Low Pass 2 Channel C = 4.7µF 20 A 6-SMD [12.1x9.1]")
      (fields (field (name "MANUFACTURER") "Murata") (field (name "PART NUMBER") "BNX024-H01L"))
      (libsource (lib "Passive") (part "BNX024H01L"))
    )
  )
  (nets
    (net (code "1") (name "+5V_TX") (class "Default")
      (node (ref "R1") (pin "1") (pinfunction "1_1") (pintype "passive"))
      (node (ref "TP8") (pin "1") (pintype "passive"))
      (node (ref "VT4") (pin "3") (pinfunction "D_3") (pintype "passive"))
    )
    (net (code "2") (name "+12V_IN") (class "Default")
      (node (ref "C3") (pin "1") (pinfunction "1_1") (pintype "passive"))
      (node (ref "C32") (pin "1") (pinfunction "1_1") (pintype "passive"))
      (node (ref "FB1") (pin "1") (pintype "passive"))
      (node (ref "R10") (pin "2") (pinfunction "2_2") (pintype "passive"))
      (node (ref "TP7") (pin "1") (pintype "passive"))
      (node (ref "VT2") (pin "2") (pinfunction "S_2") (pintype "passive"))
    )
    (net (code "3") (name "+12V_TX") (class "Default")
      (node (ref "C24") (pin "2") (pinfunction "2_2") (pintype "passive"))
      (node (ref "C27") (pin "2") (pinfunction "2_2") (pintype "passive"))
      (node (ref "C4") (pin "1") (pinfunction "1_1") (pintype "passive"))
      (node (ref "FB3") (pin "2") (pintype "passive"))
      (node (ref "K1") (pin "2") (pinfunction "COIL2_2") (pintype "passive"))
      (node (ref "K2") (pin "2") (pinfunction "COIL2_2") (pintype "passive"))
      (node (ref "R12") (pin "1") (pinfunction "1_1") (pintype "passive"))
      (node (ref "R16") (pin "1") (pinfunction "1_1") (pintype "passive"))
      (node (ref "R9") (pin "2") (pinfunction "2_2") (pintype "passive"))
      (node (ref "TP4") (pin "1") (pintype "passive"))
      (node (ref "VD10") (pin "CA") (pintype "passive"))
      (node (ref "VD6") (pin "CA") (pintype "passive"))
      (node (ref "VT2") (pin "3") (pinfunction "D_3") (pintype "passive"))
    )
    (net (code "4") (name "+24V_IN") (class "Default")
      (node (ref "C1") (pin "2") (pinfunction "2_2") (pintype "passive"))
      (node (ref "C11") (pin "1") (pinfunction "1_1") (pintype "passive"))
      (node (ref "C12") (pin "1") (pinfunction "1_1") (pintype "passive"))
      (node (ref "C13") (pin "1") (pinfunction "1_1") (pintype "passive"))
      (node (ref "C14") (pin "1") (pinfunction "1_1") (pintype "passive"))
      (node (ref "C16") (pin "1") (pinfunction "1_1") (pintype "passive"))
      (node (ref "C2") (pin "1") (pinfunction "1_1") (pintype "passive"))
      (node (ref "L1") (pin "1") (pinfunction "1_1") (pintype "passive"))
      (node (ref "R27") (pin "1") (pinfunction "1_1") (pintype "passive"))
      (node (ref "TP5") (pin "1") (pintype "passive"))
      (node (ref "TP6") (pin "1") (pintype "passive"))
      (node (ref "TR1") (pin "4") (pintype "passive"))
    )
    (net (code "5") (name "+V_FAN") (class "Default")
      (node (ref "C31") (pin "1") (pinfunction "1_1") (pintype "passive"))
      (node (ref "C33") (pin "1") (pinfunction "1_1") (pintype "passive"))
      (node (ref "FB2") (pin "1") (pintype "passive"))
      (node (ref "R28") (pin "1") (pinfunction "1_1") (pintype "passive"))
      (node (ref "TP1") (pin "1") (pintype "passive"))
      (node (ref "X4") (pin "1") (pinfunction "1_1") (pintype "passive"))
    )
    (net (code "6") (name "BIAS_A") (class "Default")
      (node (ref "C18") (pin "1") (pinfunction "1_1") (pintype "passive"))
      (node (ref "C8") (pin "1") (pinfunction "1_1") (pintype "passive"))
      (node (ref "R18") (pin "1") (pinfunction "1_1") (pintype "passive"))
      (node (ref "R7") (pin "2") (pinfunction "WIPER_2") (pintype "passive"))
    )
    (net (code "7") (name "BIAS_B") (class "Default")
      (node (ref "C19") (pin "1") (pinfunction "1_1") (pintype "passive"))
      (node (ref "C9") (pin "1") (pinfunction "1_1") (pintype "passive"))
      (node (ref "R19") (pin "1") (pinfunction "1_1") (pintype "passive"))
      (node (ref "R8") (pin "2") (pinfunction "WIPER_2") (pintype "passive"))
    )
    (net (code "8") (name "GND") (class "Default")
      (node (ref "C1") (pin "1") (pinfunction "1_1") (pintype "passive"))
      (node (ref "C10") (pin "2") (pinfunction "2_2") (pintype "passive"))
      (node (ref "C11") (pin "2") (pinfunction "2_2") (pintype "passive"))
      (node (ref "C12") (pin "2") (pinfunction "2_2") (pintype "passive"))
      (node (ref "C13") (pin "2") (pinfunction "2_2") (pintype "passive"))
      (node (ref "C14") (pin "2") (pinfunction "2_2") (pintype "passive"))
      (node (ref "C15") (pin "2") (pinfunction "2_2") (pintype "passive"))
      (node (ref "C16") (pin "2") (pinfunction "2_2") (pintype "passive"))
      (node (ref "C17") (pin "2") (pinfunction "2_2") (pintype "passive"))
      (node (ref "C18") (pin "2") (pinfunction "2_2") (pintype "passive"))
      (node (ref "C19") (pin "2") (pinfunction "2_2") (pintype "passive"))
      (node (ref "C2") (pin "2") (pinfunction "2_2") (pintype "passive"))
      (node (ref "C22") (pin "2") (pinfunction "2_2") (pintype "passive"))
      (node (ref "C24") (pin "1") (pinfunction "1_1") (pintype "passive"))
      (node (ref "C27") (pin "1") (pinfunction "1_1") (pintype "passive"))
      (node (ref "C28") (pin "2") (pinfunction "2_2") (pintype "passive"))
      (node (ref "C3") (pin "2") (pinfunction "2_2") (pintype "passive"))
      (node (ref "C31") (pin "2") (pinfunction "2_2") (pintype "passive"))
      (node (ref "C32") (pin "2") (pinfunction "2_2") (pintype "passive"))
      (node (ref "C33") (pin "2") (pinfunction "2_2") (pintype "passive"))
      (node (ref "C4") (pin "2") (pinfunction "2_2") (pintype "passive"))
      (node (ref "C5") (pin "2") (pinfunction "2_2") (pintype "passive"))
      (node (ref "C6") (pin "2") (pinfunction "2_2") (pintype "passive"))
      (node (ref "C7") (pin "2") (pinfunction "2_2") (pintype "passive"))
      (node (ref "C8") (pin "2") (pinfunction "2_2") (pintype "passive"))
      (node (ref "C9") (pin "2") (pinfunction "2_2") (pintype "passive"))
      (node (ref "D3") (pin "3") (pinfunction "GND_3") (pintype "passive"))
      (node (ref "D3") (pin "5") (pinfunction "~{ON/}OFF_5") (pintype "passive"))
      (node (ref "D3") (pin "6") (pinfunction "TP_6") (pintype "passive"))
      (node (ref "D4") (pin "3") (pinfunction "GND(TAB)_3") (pintype "passive"))
      (node (ref "HG1") (pin "CA") (pinfunction "Cathode_CA") (pintype "passive"))
      (node (ref "HG2") (pin "CA") (pinfunction "Cathode_CA") (pintype "passive"))
      (node (ref "HG3") (pin "CA") (pinfunction "Cathode_CA") (pintype "passive"))
      (node (ref "HG4") (pin "CA") (pinfunction "Cathode_CA") (pintype "passive"))
      (node (ref "K1") (pin "1") (pinfunction "COIL1_1") (pintype "passive"))
      (node (ref "K2") (pin "1") (pinfunction "COIL1_1") (pintype "passive"))
      (node (ref "R14") (pin "1") (pinfunction "1_1") (pintype "passive"))
      (node (ref "R17") (pin "1") (pinfunction "1_1") (pintype "passive"))
      (node (ref "R2") (pin "2") (pinfunction "2_2") (pintype "passive"))
      (node (ref "R23") (pin "1") (pinfunction "1_1") (pintype "passive"))
      (node (ref "R32") (pin "2") (pinfunction "2_2") (pintype "passive"))
      (node (ref "R5") (pin "1") (pinfunction "1_1") (pintype "passive"))
      (node (ref "R7") (pin "3") (pinfunction "CW_3") (pintype "passive"))
      (node (ref "R8") (pin "3") (pinfunction "CW_3") (pintype "passive"))
      (node (ref "TP3") (pin "1") (pintype "passive"))
      (node (ref "TR1") (pin "1") (pintype "passive"))
      (node (ref "TR2") (pin "1") (pintype "passive"))
      (node (ref "VD10") (pin "AN") (pintype "passive"))
      (node (ref "VD2") (pin "AN") (pintype "passive"))
      (node (ref "VD5") (pin "1") (pintype "passive"))
      (node (ref "VD5") (pin "2") (pintype "passive"))
      (node (ref "VD6") (pin "AN") (pintype "passive"))
      (node (ref "VD7") (pin "1") (pintype "passive"))
      (node (ref "VD7") (pin "2") (pintype "passive"))
      (node (ref "VD8") (pin "1") (pintype "passive"))
      (node (ref "VD8") (pin "2") (pintype "passive"))
      (node (ref "VT1") (pin "5") (pinfunction "S_5") (pintype "passive"))
      (node (ref "VT3") (pin "2") (pinfunction "S_2") (pintype "passive"))
      (node (ref "VT5") (pin "2") (pinfunction "E_2") (pintype "passive"))
      (node (ref "X1") (pin "2") (pinfunction "2_2") (pintype "passive"))
      (node (ref "X1") (pin "3") (pinfunction "3_3") (pintype "passive"))
      (node (ref "X2") (pin "2") (pinfunction "2_2") (pintype "passive"))
      (node (ref "X3") (pin "2") (pinfunction "2_2") (pintype "passive"))
      (node (ref "X5") (pin "2") (pinfunction "2_2") (pintype "passive"))
      (node (ref "X6") (pin "2") (pinfunction "2_2") (pintype "passive"))
      (node (ref "X7") (pin "2") (pinfunction "2_2") (pintype "passive"))
      (node (ref "X9") (pin "2") (pinfunction "2_2") (pintype "passive"))
      (node (ref "Z1") (pin "4") (pinfunction "OUT-_4") (pintype "passive"))
      (node (ref "Z1") (pin "5") (pinfunction "OUT-_5") (pintype "passive"))
      (node (ref "Z1") (pin "6") (pinfunction "OUT-_6") (pintype "passive"))
    )
    (net (code "9") (name "GND_IN") (class "Default")
      (node (ref "VD1") (pin "AN") (pintype "passive"))
      (node (ref "X8") (pin "2") (pinfunction "2_2") (pintype "passive"))
      (node (ref "X8") (pin "MP") (pinfunction "MP_MP") (pintype "passive"))
      (node (ref "Z1") (pin "3") (pinfunction "IN-_3") (pintype "passive"))
    )
    (net (code "10") (name "Net-(C10-Pad1)") (class "Default")
      (node (ref "C10") (pin "1") (pinfunction "1_1") (pintype "passive"))
      (node (ref "FB2") (pin "2") (pintype "passive"))
      (node (ref "L4") (pin "2") (pinfunction "2_2") (pintype "passive"))
      (node (ref "R30") (pin "1") (pinfunction "1_1") (pintype "passive"))
    )
    (net (code "11") (name "Net-(C20-Pad1)") (class "Default")
      (node (ref "C20") (pin "1") (pinfunction "1_1") (pintype "passive"))
      (node (ref "TR2") (pin "4") (pintype "passive"))
    )
    (net (code "12") (name "Net-(C20-Pad2)") (class "Default")
      (node (ref "C20") (pin "2") (pinfunction "2_2") (pintype "passive"))
      (node (ref "R20") (pin "1") (pinfunction "1_1") (pintype "passive"))
    )
    (net (code "13") (name "Net-(C21-Pad2)") (class "Default")
      (node (ref "C21") (pin "2") (pinfunction "2_2") (pintype "passive"))
      (node (ref "R21") (pin "1") (pinfunction "1_1") (pintype "passive"))
    )
    (net (code "14") (name "Net-(C23-Pad2)") (class "Default")
      (node (ref "C23") (pin "2") (pinfunction "2_2") (pintype "passive"))
      (node (ref "X7") (pin "1") (pinfunction "1_1") (pintype "passive"))
    )
    (net (code "15") (name "Net-(C25-Pad1)") (class "Default")
      (node (ref "C25") (pin "1") (pinfunction "1_1") (pintype "passive"))
      (node (ref "TR2") (pin "3") (pintype "passive"))
    )
    (net (code "16") (name "Net-(C25-Pad2)") (class "Default")
      (node (ref "C25") (pin "2") (pinfunction "2_2") (pintype "passive"))
      (node (ref "R26") (pin "1") (pinfunction "1_1") (pintype "passive"))
    )
    (net (code "17") (name "Net-(C26-Pad1)") (class "Default")
      (node (ref "C26") (pin "1") (pinfunction "1_1") (pintype "passive"))
      (node (ref "TR1") (pin "3") (pintype "passive"))
      (node (ref "VT1") (pin "2") (pinfunction "S_2") (pintype "passive"))
    )
    (net (code "18") (name "Net-(C26-Pad2)") (class "Default")
      (node (ref "C26") (pin "2") (pinfunction "2_2") (pintype "passive"))
      (node (ref "R22") (pin "1") (pinfunction "1_1") (pintype "passive"))
    )
    (net (code "19") (name "Net-(D1-ADJ)") (class "Default")
      (node (ref "D1") (pin "1") (pinfunction "ADJ_1") (pintype "passive"))
      (node (ref "R3") (pin "1") (pinfunction "1_1") (pintype "passive"))
      (node (ref "R5") (pin "2") (pinfunction "2_2") (pintype "passive"))
    )
    (net (code "20") (name "Net-(D1-VIN)") (class "Default")
      (node (ref "C15") (pin "1") (pinfunction "1_1") (pintype "passive"))
      (node (ref "D1") (pin "3") (pinfunction "VIN_3") (pintype "passive"))
      (node (ref "FB5") (pin "1") (pintype "passive"))
    )
    (net (code "21") (name "Net-(D1-VOUT)") (class "Default")
      (node (ref "D1") (pin "2") (pinfunction "VOUT_2") (pintype "passive"))
      (node (ref "FB1") (pin "2") (pintype "passive"))
      (node (ref "R3") (pin "2") (pinfunction "2_2") (pintype "passive"))
    )
    (net (code "22") (name "Net-(D2-A)") (class "Default")
      (node (ref "D2") (pin "3") (pinfunction "A_3") (pintype "passive"))
      (node (ref "R6") (pin "2") (pinfunction "2_2") (pintype "passive"))
      (node (ref "X1") (pin "1") (pinfunction "1_1") (pintype "passive"))
    )
    (net (code "23") (name "Net-(D2-C)") (class "Default")
      (node (ref "C17") (pin "1") (pinfunction "1_1") (pintype "passive"))
      (node (ref "D2") (pin "1") (pinfunction "C_1") (pintype "passive"))
      (node (ref "R1") (pin "2") (pinfunction "2_2") (pintype "passive"))
      (node (ref "R4") (pin "1") (pinfunction "1_1") (pintype "passive"))
      (node (ref "R7") (pin "1") (pinfunction "CCW_1") (pintype "passive"))
      (node (ref "R8") (pin "1") (pinfunction "CCW_1") (pintype "passive"))
    )
    (net (code "24") (name "Net-(D2-REF)") (class "Default")
      (node (ref "D2") (pin "2") (pinfunction "REF_2") (pintype "passive"))
      (node (ref "R4") (pin "2") (pinfunction "2_2") (pintype "passive"))
      (node (ref "R6") (pin "1") (pinfunction "1_1") (pintype "passive"))
    )
    (net (code "25") (name "Net-(D3-FB)") (class "Default")
      (node (ref "D3") (pin "4") (pinfunction "FB_4") (pintype "passive"))
      (node (ref "R2") (pin "1") (pinfunction "1_1") (pintype "passive"))
      (node (ref "R30") (pin "2") (pinfunction "2_2") (pintype "passive"))
    )
    (net (code "26") (name "Net-(D3-Vin)") (class "Default")
      (node (ref "C22") (pin "1") (pinfunction "1_1") (pintype "passive"))
      (node (ref "D3") (pin "1") (pinfunction "Vin_1") (pintype "passive"))
      (node (ref "FB6") (pin "1") (pintype "passive"))
    )
    (net (code "27") (name "Net-(D3-Vout)") (class "Default")
      (node (ref "D3") (pin "2") (pinfunction "Vout_2") (pintype "passive"))
      (node (ref "L4") (pin "1") (pinfunction "1_1") (pintype "passive"))
      (node (ref "VD2") (pin "CA") (pintype "passive"))
    )
    (net (code "28") (name "Net-(D4-ADJ)") (class "Default")
      (node (ref "D4") (pin "5") (pinfunction "ADJ_5") (pintype "passive"))
      (node (ref "R31") (pin "2") (pinfunction "2_2") (pintype "passive"))
      (node (ref "R32") (pin "1") (pinfunction "1_1") (pintype "passive"))
    )
    (net (code "29") (name "Net-(D4-EN)") (class "Default")
      (node (ref "D4") (pin "1") (pinfunction "EN_1") (pintype "passive"))
      (node (ref "R25") (pin "2") (pinfunction "2_2") (pintype "passive"))
    )
    (net (code "30") (name "Net-(D4-VIN)") (class "Default")
      (node (ref "D4") (pin "2") (pinfunction "VIN_2") (pintype "passive"))
      (node (ref "FB3") (pin "1") (pintype "passive"))
      (node (ref "R25") (pin "1") (pinfunction "1_1") (pintype "passive"))
    )
    (net (code "31") (name "Net-(D4-VOUT)") (class "Default")
      (node (ref "D4") (pin "4") (pinfunction "VOUT_4") (pintype "passive"))
      (node (ref "FB4") (pin "2") (pintype "passive"))
      (node (ref "R11") (pin "2") (pinfunction "2_2") (pintype "passive"))
      (node (ref "R31") (pin "1") (pinfunction "1_1") (pintype "passive"))
    )
    (net (code "32") (name "Net-(F1-Pad1)") (class "Default")
      (node (ref "F1") (pin "1") (pinfunction "1_1") (pintype "passive"))
      (node (ref "X8") (pin "1") (pinfunction "1_1") (pintype "passive"))
    )
    (net (code "33") (name "Net-(FB7-Pad2)") (class "Default")
      (node (ref "FB7") (pin "2") (pintype "passive"))
      (node (ref "X4") (pin "2") (pinfunction "2_2") (pintype "passive"))
      (node (ref "X5") (pin "1") (pinfunction "1_1") (pintype "passive"))
    )
    (net (code "34") (name "Net-(HG1-Anode)") (class "Default")
      (node (ref "HG1") (pin "AN") (pinfunction "Anode_AN") (pintype "passive"))
      (node (ref "R11") (pin "1") (pinfunction "1_1") (pintype "passive"))
    )
    (net (code "35") (name "Net-(HG2-Anode)") (class "Default")
      (node (ref "HG2") (pin "AN") (pinfunction "Anode_AN") (pintype "passive"))
      (node (ref "R12") (pin "2") (pinfunction "2_2") (pintype "passive"))
    )
    (net (code "36") (name "Net-(HG3-Anode)") (class "Default")
      (node (ref "HG3") (pin "AN") (pinfunction "Anode_AN") (pintype "passive"))
      (node (ref "R27") (pin "2") (pinfunction "2_2") (pintype "passive"))
    )
    (net (code "37") (name "Net-(HG4-Anode)") (class "Default")
      (node (ref "HG4") (pin "AN") (pinfunction "Anode_AN") (pintype "passive"))
      (node (ref "R28") (pin "2") (pinfunction "2_2") (pintype "passive"))
    )
    (net (code "38") (name "Net-(K1-1-COM)") (class "Default")
      (node (ref "K1") (pin "5") (pinfunction "1-COM_5") (pintype "passive"))
      (node (ref "K1") (pin "6") (pinfunction "2-COM_6") (pintype "passive"))
      (node (ref "X6") (pin "1") (pinfunction "1_1") (pintype "passive"))
    )
    (net (code "39") (name "Net-(K1-1-NC)") (class "Default")
      (node (ref "K1") (pin "3") (pinfunction "1-NC_3") (pintype "passive"))
      (node (ref "K1") (pin "4") (pinfunction "2-NC_4") (pintype "passive"))
      (node (ref "K2") (pin "3") (pinfunction "1-NC_3") (pintype "passive"))
      (node (ref "K2") (pin "4") (pinfunction "2-NC_4") (pintype "passive"))
    )
    (net (code "40") (name "Net-(K1-2-NO-Pad7)") (class "Default")
      (node (ref "K1") (pin "7") (pinfunction "2-NO_7") (pintype "passive"))
      (node (ref "K1") (pin "8") (pinfunction "2-NO_8") (pintype "passive"))
      (node (ref "TR1") (pin "2") (pintype "passive"))
    )
    (net (code "41") (name "Net-(K2-1-COM)") (class "Default")
      (node (ref "C23") (pin "1") (pinfunction "1_1") (pintype "passive"))
      (node (ref "C28") (pin "1") (pinfunction "1_1") (pintype "passive"))
      (node (ref "K2") (pin "5") (pinfunction "1-COM_5") (pintype "passive"))
      (node (ref "K2") (pin "6") (pinfunction "2-COM_6") (pintype "passive"))
    )
    (net (code "42") (name "Net-(K2-2-NO-Pad7)") (class "Default")
      (node (ref "K2") (pin "7") (pinfunction "2-NO_7") (pintype "passive"))
      (node (ref "K2") (pin "8") (pinfunction "2-NO_8") (pintype "passive"))
      (node (ref "R13") (pin "1") (pinfunction "1_1") (pintype "passive"))
      (node (ref "R14") (pin "2") (pinfunction "2_2") (pintype "passive"))
    )
    (net (code "43") (name "Net-(R9-Pad1)") (class "Default")
      (node (ref "R9") (pin "1") (pinfunction "1_1") (pintype "passive"))
      (node (ref "X2") (pin "1") (pinfunction "1_1") (pintype "passive"))
    )
    (net (code "44") (name "Net-(R13-Pad2)") (class "Default")
      (node (ref "R13") (pin "2") (pinfunction "2_2") (pintype "passive"))
      (node (ref "R23") (pin "2") (pinfunction "2_2") (pintype "passive"))
      (node (ref "TR2") (pin "2") (pintype "passive"))
    )
    (net (code "45") (name "Net-(R15-Pad2)") (class "Default")
      (node (ref "R15") (pin "2") (pinfunction "2_2") (pintype "passive"))
      (node (ref "VD3") (pin "AN") (pintype "passive"))
    )
    (net (code "46") (name "Net-(R18-Pad2)") (class "Default")
      (node (ref "R18") (pin "2") (pinfunction "2_2") (pintype "passive"))
      (node (ref "R20") (pin "2") (pinfunction "2_2") (pintype "passive"))
      (node (ref "R21") (pin "2") (pinfunction "2_2") (pintype "passive"))
      (node (ref "R24") (pin "2") (pinfunction "2_2") (pintype "passive"))
      (node (ref "VD7") (pin "3") (pintype "passive"))
      (node (ref "VT1") (pin "3") (pinfunction "G_3") (pintype "passive"))
    )
    (net (code "47") (name "Net-(R19-Pad2)") (class "Default")
      (node (ref "R19") (pin "2") (pinfunction "2_2") (pintype "passive"))
      (node (ref "R22") (pin "2") (pinfunction "2_2") (pintype "passive"))
      (node (ref "R24") (pin "1") (pinfunction "1_1") (pintype "passive"))
      (node (ref "R26") (pin "2") (pinfunction "2_2") (pintype "passive"))
      (node (ref "VD8") (pin "3") (pintype "passive"))
      (node (ref "VT1") (pin "4") (pinfunction "G_4") (pintype "passive"))
    )
    (net (code "48") (name "Net-(R29-Pad2)") (class "Default")
      (node (ref "R29") (pin "2") (pinfunction "2_2") (pintype "passive"))
      (node (ref "VD4") (pin "AN") (pintype "passive"))
    )
    (net (code "49") (name "Net-(VD3-PadCA)") (class "Default")
      (node (ref "VD3") (pin "CA") (pintype "passive"))
      (node (ref "X3") (pin "1") (pinfunction "1_1") (pintype "passive"))
    )
    (net (code "50") (name "Net-(VD4-PadCA)") (class "Default")
      (node (ref "VD4") (pin "CA") (pintype "passive"))
      (node (ref "X9") (pin "1") (pinfunction "1_1") (pintype "passive"))
    )
    (net (code "51") (name "Net-(VT1-D)") (class "Default")
      (node (ref "C21") (pin "1") (pinfunction "1_1") (pintype "passive"))
      (node (ref "TR1") (pin "5") (pintype "passive"))
      (node (ref "VT1") (pin "1") (pinfunction "D_1") (pintype "passive"))
    )
    (net (code "52") (name "Net-(VT2-G)") (class "Default")
      (node (ref "C7") (pin "1") (pinfunction "1_1") (pintype "passive"))
      (node (ref "R10") (pin "1") (pinfunction "1_1") (pintype "passive"))
      (node (ref "R15") (pin "1") (pinfunction "1_1") (pintype "passive"))
      (node (ref "VD5") (pin "3") (pintype "passive"))
      (node (ref "VT2") (pin "1") (pinfunction "G_1") (pintype "passive"))
    )
    (net (code "53") (name "Net-(VT3-D)") (class "Default")
      (node (ref "FB7") (pin "1") (pintype "passive"))
      (node (ref "VT3") (pin "3") (pinfunction "D_3") (pintype "passive"))
    )
    (net (code "54") (name "Net-(VT3-G)") (class "Default")
      (node (ref "R16") (pin "2") (pinfunction "2_2") (pintype "passive"))
      (node (ref "R17") (pin "2") (pinfunction "2_2") (pintype "passive"))
      (node (ref "VT3") (pin "1") (pinfunction "G_1") (pintype "passive"))
    )
    (net (code "55") (name "Net-(VT4-G)") (class "Default")
      (node (ref "R34") (pin "1") (pinfunction "1_1") (pintype "passive"))
      (node (ref "R35") (pin "1") (pinfunction "1_1") (pintype "passive"))
      (node (ref "VT4") (pin "1") (pinfunction "G_1") (pintype "passive"))
    )
    (net (code "56") (name "Net-(VT4-S)") (class "Default")
      (node (ref "C5") (pin "1") (pinfunction "1_1") (pintype "passive"))
      (node (ref "C6") (pin "1") (pinfunction "1_1") (pintype "passive"))
      (node (ref "FB4") (pin "1") (pintype "passive"))
      (node (ref "R33") (pin "2") (pinfunction "2_2") (pintype "passive"))
      (node (ref "R34") (pin "2") (pinfunction "2_2") (pintype "passive"))
      (node (ref "TP2") (pin "1") (pintype "passive"))
      (node (ref "VT4") (pin "2") (pinfunction "S_2") (pintype "passive"))
    )
    (net (code "57") (name "Net-(VT5-B)") (class "Default")
      (node (ref "R29") (pin "1") (pinfunction "1_1") (pintype "passive"))
      (node (ref "R33") (pin "1") (pinfunction "1_1") (pintype "passive"))
      (node (ref "VT5") (pin "1") (pinfunction "B_1") (pintype "passive"))
    )
    (net (code "58") (name "Net-(VT5-C)") (class "Default")
      (node (ref "R35") (pin "2") (pinfunction "2_2") (pintype "passive"))
      (node (ref "VT5") (pin "3") (pinfunction "C_3") (pintype "passive"))
    )
    (net (code "59") (name "Net-(Z1-IN+)") (class "Default")
      (node (ref "F1") (pin "2") (pinfunction "2_2") (pintype "passive"))
      (node (ref "VD1") (pin "CA") (pintype "passive"))
      (node (ref "Z1") (pin "1") (pinfunction "IN+_1") (pintype "passive"))
    )
    (net (code "60") (name "Net-(Z1-OUT+)") (class "Default")
      (node (ref "FB5") (pin "2") (pintype "passive"))
      (node (ref "FB6") (pin "2") (pintype "passive"))
      (node (ref "L1") (pin "2") (pinfunction "2_2") (pintype "passive"))
      (node (ref "Z1") (pin "2") (pinfunction "OUT+_2") (pintype "passive"))
    )
  )
)
